# ePro.net
KiCad netlist of a schematic drawn in EAGLE
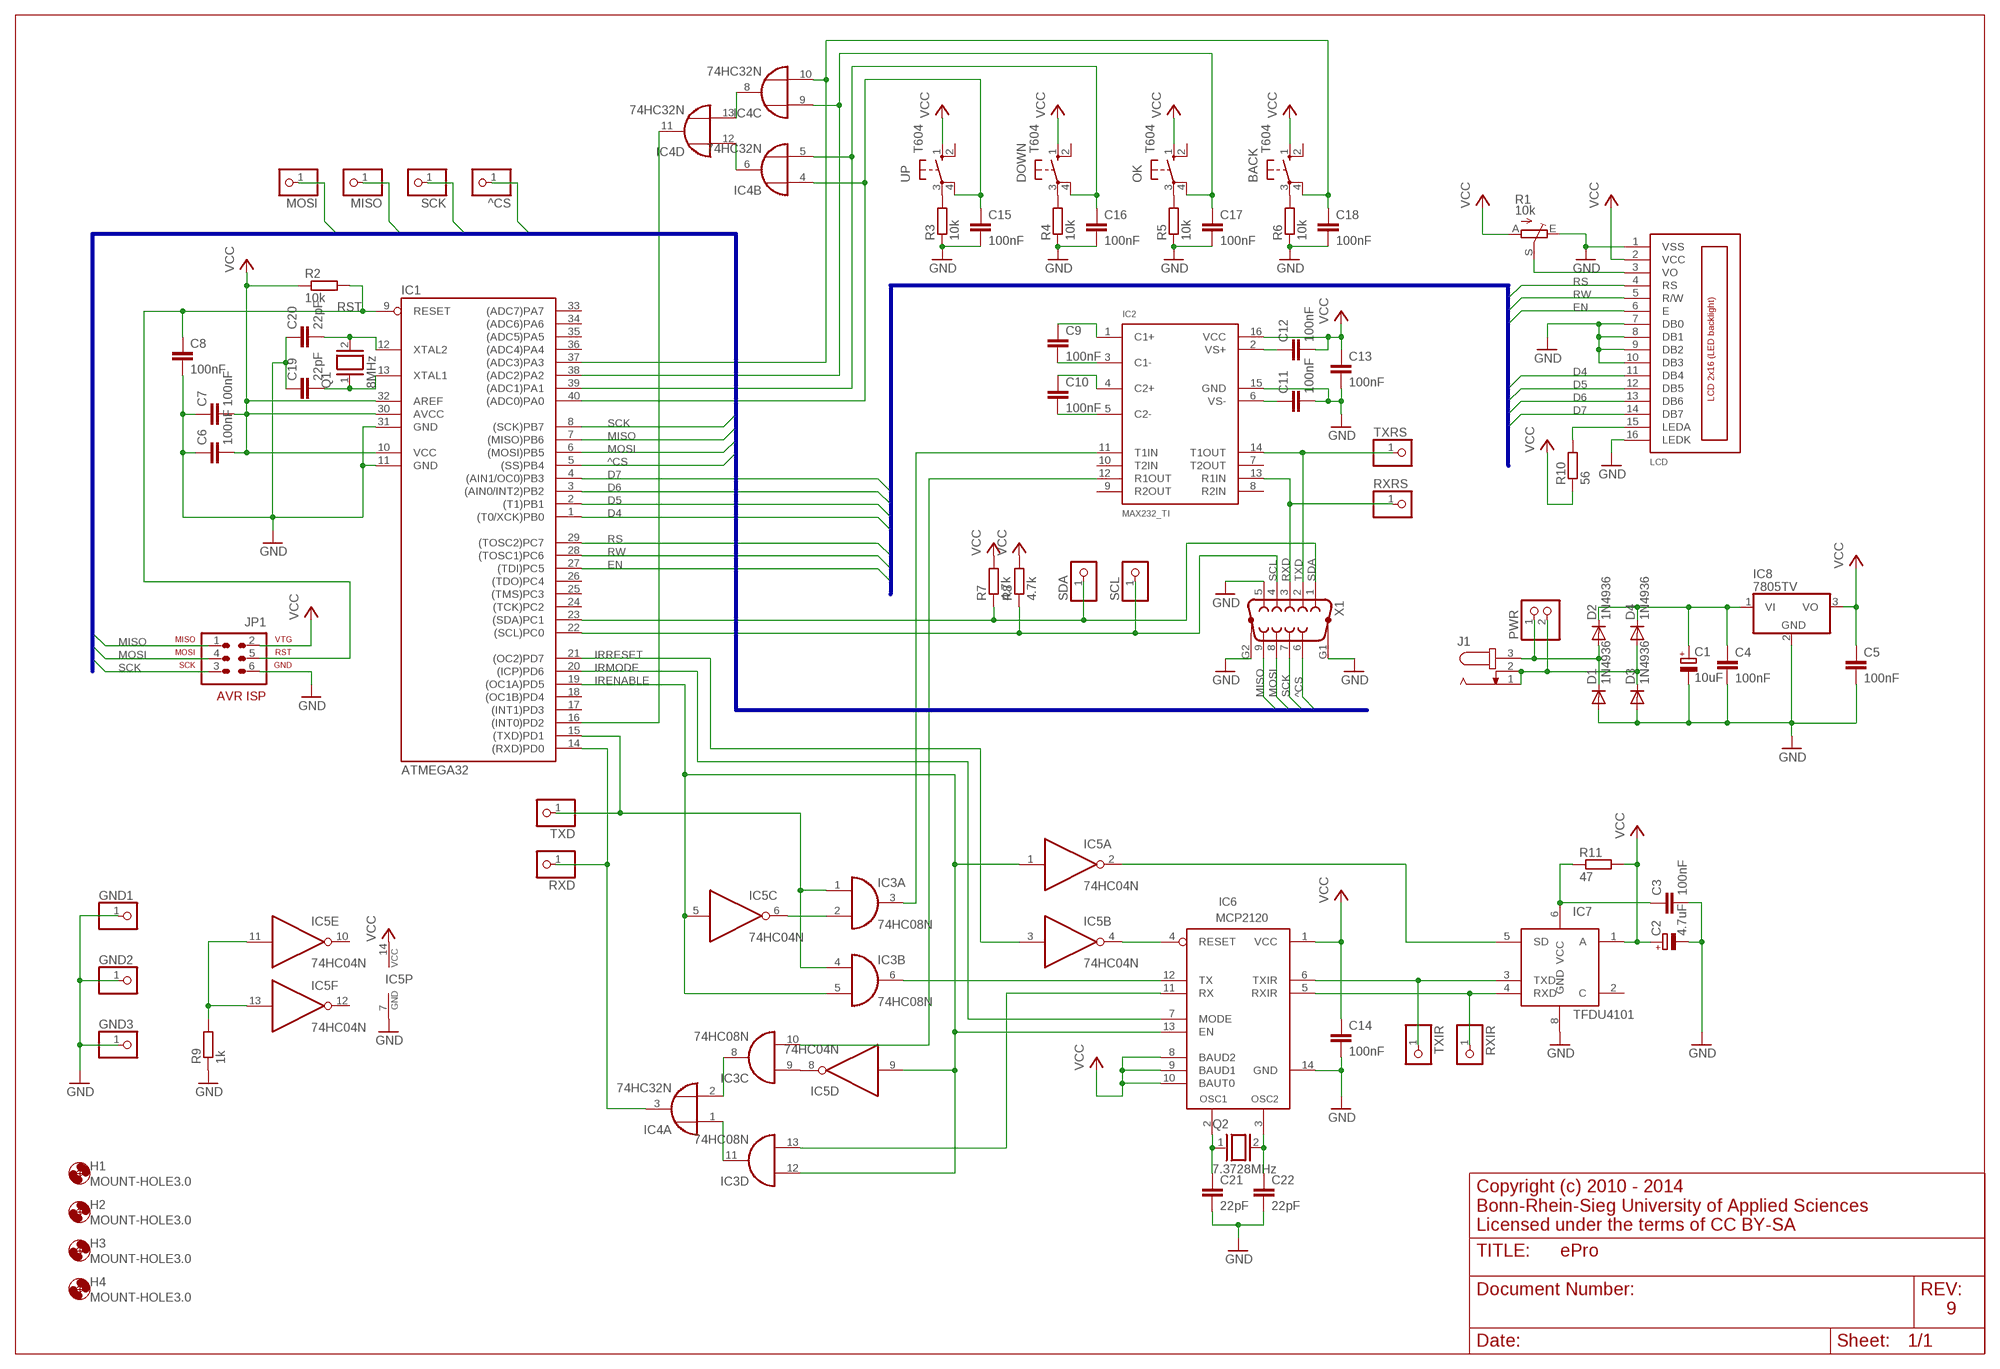
[diagram p0: schematic, sheet 1]

(export (version "E")
  (design (tool "Eeschema 10.0.6"))
  (components
    (comp (ref "BACK")
      (value "T604")
      (footprint "eagle-import:T602_604")
      (libsource (lib "eagle-import") (part "T604"))
    )
    (comp (ref "C1")
      (value "10uF")
      (footprint "eagle-import:B45181B")
      (libsource (lib "eagle-import") (part "CPOL-EUB45181B"))
    )
    (comp (ref "C2")
      (value "4.7uF")
      (footprint "eagle-import:B45181B")
      (libsource (lib "eagle-import") (part "CPOL-EUB45181B"))
    )
    (comp (ref "C3")
      (value "100nF")
      (footprint "eagle-import:C025-024X044")
      (libsource (lib "eagle-import") (part "C-EU025-024X044"))
    )
    (comp (ref "C4")
      (value "100nF")
      (footprint "eagle-import:C025-024X044")
      (libsource (lib "eagle-import") (part "C-EU025-024X044"))
    )
    (comp (ref "C5")
      (value "100nF")
      (footprint "eagle-import:C025-024X044")
      (libsource (lib "eagle-import") (part "C-EU025-024X044"))
    )
    (comp (ref "C6")
      (value "100nF")
      (footprint "eagle-import:C025-024X044")
      (libsource (lib "eagle-import") (part "C-EU025-024X044"))
    )
    (comp (ref "C7")
      (value "100nF")
      (footprint "eagle-import:C025-024X044")
      (libsource (lib "eagle-import") (part "C-EU025-024X044"))
    )
    (comp (ref "C8")
      (value "100nF")
      (footprint "eagle-import:C025-024X044")
      (libsource (lib "eagle-import") (part "C-EU025-024X044"))
    )
    (comp (ref "C9")
      (value "100nF")
      (footprint "eagle-import:C025-024X044")
      (libsource (lib "eagle-import") (part "C-EU025-024X044"))
    )
    (comp (ref "C10")
      (value "100nF")
      (footprint "eagle-import:C025-024X044")
      (libsource (lib "eagle-import") (part "C-EU025-024X044"))
    )
    (comp (ref "C11")
      (value "100nF")
      (footprint "eagle-import:C025-024X044")
      (libsource (lib "eagle-import") (part "C-EU025-024X044"))
    )
    (comp (ref "C12")
      (value "100nF")
      (footprint "eagle-import:C025-024X044")
      (libsource (lib "eagle-import") (part "C-EU025-024X044"))
    )
    (comp (ref "C13")
      (value "100nF")
      (footprint "eagle-import:C025-024X044")
      (libsource (lib "eagle-import") (part "C-EU025-024X044"))
    )
    (comp (ref "C14")
      (value "100nF")
      (footprint "eagle-import:C025-024X044")
      (libsource (lib "eagle-import") (part "C-EU025-024X044"))
    )
    (comp (ref "C15")
      (value "100nF")
      (footprint "eagle-import:C025-024X044")
      (libsource (lib "eagle-import") (part "C-EU025-024X044"))
    )
    (comp (ref "C16")
      (value "100nF")
      (footprint "eagle-import:C025-024X044")
      (libsource (lib "eagle-import") (part "C-EU025-024X044"))
    )
    (comp (ref "C17")
      (value "100nF")
      (footprint "eagle-import:C025-024X044")
      (libsource (lib "eagle-import") (part "C-EU025-024X044"))
    )
    (comp (ref "C18")
      (value "100nF")
      (footprint "eagle-import:C025-024X044")
      (libsource (lib "eagle-import") (part "C-EU025-024X044"))
    )
    (comp (ref "C19")
      (value "22pF")
      (footprint "eagle-import:C025-024X044")
      (libsource (lib "eagle-import") (part "resistor_C-EU025-024X044"))
    )
    (comp (ref "C20")
      (value "22pF")
      (footprint "eagle-import:C025-024X044")
      (libsource (lib "eagle-import") (part "resistor_C-EU025-024X044"))
    )
    (comp (ref "C21")
      (value "22pF")
      (footprint "eagle-import:C025-024X044")
      (libsource (lib "eagle-import") (part "resistor_C-EU025-024X044"))
    )
    (comp (ref "C22")
      (value "22pF")
      (footprint "eagle-import:C025-024X044")
      (libsource (lib "eagle-import") (part "resistor_C-EU025-024X044"))
    )
    (comp (ref "D1")
      (value "1N4936")
      (footprint "eagle-import:DO41-10")
      (libsource (lib "eagle-import") (part "1N4936"))
    )
    (comp (ref "D2")
      (value "1N4936")
      (footprint "eagle-import:DO41-10")
      (libsource (lib "eagle-import") (part "1N4936"))
    )
    (comp (ref "D3")
      (value "1N4936")
      (footprint "eagle-import:DO41-10")
      (libsource (lib "eagle-import") (part "1N4936"))
    )
    (comp (ref "D4")
      (value "1N4936")
      (footprint "eagle-import:DO41-10")
      (libsource (lib "eagle-import") (part "1N4936"))
    )
    (comp (ref "DOWN")
      (value "T604")
      (footprint "eagle-import:T602_604")
      (libsource (lib "eagle-import") (part "T604"))
    )
    (comp (ref "GND1")
      (value "PINHD-1X1")
      (footprint "eagle-import:1X01")
      (libsource (lib "eagle-import") (part "PINHD-1X1"))
    )
    (comp (ref "GND2")
      (value "PINHD-1X1")
      (footprint "eagle-import:1X01")
      (libsource (lib "eagle-import") (part "PINHD-1X1"))
    )
    (comp (ref "GND3")
      (value "PINHD-1X1")
      (footprint "eagle-import:1X01")
      (libsource (lib "eagle-import") (part "PINHD-1X1"))
    )
    (comp (ref "H1")
      (value "MOUNT-HOLE3.0")
      (footprint "eagle-import:3,0")
      (libsource (lib "eagle-import") (part "MOUNT-HOLE3.0"))
    )
    (comp (ref "H2")
      (value "MOUNT-HOLE3.0")
      (footprint "eagle-import:3,0")
      (libsource (lib "eagle-import") (part "MOUNT-HOLE3.0"))
    )
    (comp (ref "H3")
      (value "MOUNT-HOLE3.0")
      (footprint "eagle-import:3,0")
      (libsource (lib "eagle-import") (part "MOUNT-HOLE3.0"))
    )
    (comp (ref "H4")
      (value "MOUNT-HOLE3.0")
      (footprint "eagle-import:3,0")
      (libsource (lib "eagle-import") (part "MOUNT-HOLE3.0"))
    )
    (comp (ref "IC1")
      (value "ATMEGA32")
      (footprint "eagle-import:DIL40")
      (libsource (lib "eagle-import") (part "MEGA32-P"))
    )
    (comp (ref "IC2")
      (value "MAX232_TI")
      (footprint "eagle-import:DIL16")
      (libsource (lib "eagle-import") (part "MAX232_TI"))
    )
    (comp (ref "IC3")
      (value "74HC08N")
      (footprint "eagle-import:DIL14")
      (libsource (lib "eagle-import") (part "7408NHC"))
    )
    (comp (ref "IC4")
      (value "74HC32N")
      (footprint "eagle-import:DIL14")
      (libsource (lib "eagle-import") (part "7432NHC"))
    )
    (comp (ref "IC5")
      (value "74HC04N")
      (footprint "eagle-import:DIL14")
      (libsource (lib "eagle-import") (part "7404NHC"))
    )
    (comp (ref "IC6")
      (value "MCP2120")
      (footprint "eagle-import:DIL14")
      (libsource (lib "eagle-import") (part "MCP2120-P"))
    )
    (comp (ref "IC7")
      (value "TFDU4101")
      (footprint "eagle-import:U")
      (libsource (lib "eagle-import") (part "TFDU4101"))
    )
    (comp (ref "IC8")
      (value "7805TV")
      (footprint "eagle-import:TO220V")
      (libsource (lib "eagle-import") (part "78TV05"))
    )
    (comp (ref "J1")
      (value "JACK-PLUG1")
      (footprint "eagle-import:SPC4078")
      (libsource (lib "eagle-import") (part "JACK-PLUG1"))
    )
    (comp (ref "JP1")
      (value "AVR-ISP-6")
      (footprint "eagle-import:AVR-ISP-6")
      (libsource (lib "eagle-import") (part "AVR-ISP-6"))
    )
    (comp (ref "LCD")
      (value "LCD_2X16_SIL")
      (footprint "eagle-import:HY-1602F")
      (libsource (lib "eagle-import") (part "LCD_2X16_SIL"))
    )
    (comp (ref "MISO")
      (value "PINHD-1X1")
      (footprint "eagle-import:1X01")
      (libsource (lib "eagle-import") (part "PINHD-1X1"))
    )
    (comp (ref "MOSI")
      (value "PINHD-1X1")
      (footprint "eagle-import:1X01")
      (libsource (lib "eagle-import") (part "PINHD-1X1"))
    )
    (comp (ref "OK")
      (value "T604")
      (footprint "eagle-import:T602_604")
      (libsource (lib "eagle-import") (part "T604"))
    )
    (comp (ref "PWR")
      (value "PINHD-1X2")
      (footprint "eagle-import:1X02")
      (libsource (lib "eagle-import") (part "PINHD-1X2"))
    )
    (comp (ref "Q1")
      (value "8MHz")
      (footprint "eagle-import:QS")
      (libsource (lib "eagle-import") (part "XTAL/S"))
    )
    (comp (ref "Q2")
      (value "7.3728MHz")
      (footprint "eagle-import:QS")
      (libsource (lib "eagle-import") (part "XTAL/S"))
    )
    (comp (ref "R1")
      (value "10k")
      (footprint "eagle-import:PT-10S")
      (libsource (lib "eagle-import") (part "TRIM_EU-PT10S"))
    )
    (comp (ref "R2")
      (value "10k")
      (footprint "eagle-import:0204_7")
      (libsource (lib "eagle-import") (part "R-EU_0204/7"))
    )
    (comp (ref "R3")
      (value "10k")
      (footprint "eagle-import:0204_7")
      (libsource (lib "eagle-import") (part "resistor_R-EU_0204/7"))
    )
    (comp (ref "R4")
      (value "10k")
      (footprint "eagle-import:0204_7")
      (libsource (lib "eagle-import") (part "resistor_R-EU_0204/7"))
    )
    (comp (ref "R5")
      (value "10k")
      (footprint "eagle-import:0204_7")
      (libsource (lib "eagle-import") (part "resistor_R-EU_0204/7"))
    )
    (comp (ref "R6")
      (value "10k")
      (footprint "eagle-import:0204_7")
      (libsource (lib "eagle-import") (part "resistor_R-EU_0204/7"))
    )
    (comp (ref "R7")
      (value "4.7k")
      (footprint "eagle-import:0204_7")
      (libsource (lib "eagle-import") (part "resistor_R-EU_0204/7"))
    )
    (comp (ref "R8")
      (value "4.7k")
      (footprint "eagle-import:0204_7")
      (libsource (lib "eagle-import") (part "resistor_R-EU_0204/7"))
    )
    (comp (ref "R9")
      (value "1k")
      (footprint "eagle-import:0204_7")
      (libsource (lib "eagle-import") (part "resistor_R-EU_0204/7"))
    )
    (comp (ref "R10")
      (value "56")
      (footprint "eagle-import:0204_7")
      (libsource (lib "eagle-import") (part "R-EU_0204/7"))
    )
    (comp (ref "R11")
      (value "47")
      (footprint "eagle-import:0204_7")
      (libsource (lib "eagle-import") (part "R-EU_0204/7"))
    )
    (comp (ref "RXD")
      (value "PINHD-1X1")
      (footprint "eagle-import:1X01")
      (libsource (lib "eagle-import") (part "PINHD-1X1"))
    )
    (comp (ref "RXIR")
      (value "PINHD-1X1")
      (footprint "eagle-import:1X01")
      (libsource (lib "eagle-import") (part "PINHD-1X1"))
    )
    (comp (ref "RXRS")
      (value "PINHD-1X1")
      (footprint "eagle-import:1X01")
      (libsource (lib "eagle-import") (part "PINHD-1X1"))
    )
    (comp (ref "SCK")
      (value "PINHD-1X1")
      (footprint "eagle-import:1X01")
      (libsource (lib "eagle-import") (part "PINHD-1X1"))
    )
    (comp (ref "SCL")
      (value "PINHD-1X1")
      (footprint "eagle-import:1X01")
      (libsource (lib "eagle-import") (part "PINHD-1X1"))
    )
    (comp (ref "SDA")
      (value "PINHD-1X1")
      (footprint "eagle-import:1X01")
      (libsource (lib "eagle-import") (part "PINHD-1X1"))
    )
    (comp (ref "TXD")
      (value "PINHD-1X1")
      (footprint "eagle-import:1X01")
      (libsource (lib "eagle-import") (part "PINHD-1X1"))
    )
    (comp (ref "TXIR")
      (value "PINHD-1X1")
      (footprint "eagle-import:1X01")
      (libsource (lib "eagle-import") (part "PINHD-1X1"))
    )
    (comp (ref "TXRS")
      (value "PINHD-1X1")
      (footprint "eagle-import:1X01")
      (libsource (lib "eagle-import") (part "PINHD-1X1"))
    )
    (comp (ref "UP")
      (value "T604")
      (footprint "eagle-import:T602_604")
      (libsource (lib "eagle-import") (part "T604"))
    )
    (comp (ref "X1")
      (value "F09HP")
      (footprint "eagle-import:F09HP")
      (libsource (lib "eagle-import") (part "F09HP"))
    )
    (comp (ref "^CS")
      (value "PINHD-1X1")
      (footprint "eagle-import:1X01")
      (libsource (lib "eagle-import") (part "PINHD-1X1"))
    )
  )
  (nets
    (net (code "1") (name "/D4") (class "Default")
      (node (ref "IC1") (pin "1") (pinfunction "(T0/XCK)PB0_1") (pintype "bidirectional"))
      (node (ref "LCD") (pin "11") (pinfunction "DB4_11") (pintype "bidirectional"))
    )
    (net (code "2") (name "/D5") (class "Default")
      (node (ref "IC1") (pin "2") (pinfunction "(T1)PB1_2") (pintype "bidirectional"))
      (node (ref "LCD") (pin "12") (pinfunction "DB5_12") (pintype "bidirectional"))
    )
    (net (code "3") (name "/D6") (class "Default")
      (node (ref "IC1") (pin "3") (pinfunction "(AIN0/INT2)PB2_3") (pintype "bidirectional"))
      (node (ref "LCD") (pin "13") (pinfunction "DB6_13") (pintype "bidirectional"))
    )
    (net (code "4") (name "/D7") (class "Default")
      (node (ref "IC1") (pin "4") (pinfunction "(AIN1/OC0)PB3_4") (pintype "bidirectional"))
      (node (ref "LCD") (pin "14") (pinfunction "DB7_14") (pintype "bidirectional"))
    )
    (net (code "5") (name "/EN") (class "Default")
      (node (ref "IC1") (pin "27") (pinfunction "(TDI)PC5_27") (pintype "bidirectional"))
      (node (ref "LCD") (pin "6") (pinfunction "E_6") (pintype "input"))
    )
    (net (code "6") (name "/IRENABLE") (class "Default")
      (node (ref "IC1") (pin "19") (pinfunction "(OC1A)PD5_19") (pintype "bidirectional"))
      (node (ref "IC3") (pin "12") (pinfunction "I0_12") (pintype "input"))
      (node (ref "IC3") (pin "5") (pinfunction "I1_5") (pintype "input"))
      (node (ref "IC5") (pin "1") (pinfunction "I_1") (pintype "input"))
      (node (ref "IC5") (pin "5") (pinfunction "I_5") (pintype "input"))
      (node (ref "IC5") (pin "9") (pinfunction "I_9") (pintype "input"))
      (node (ref "IC6") (pin "13") (pinfunction "EN_13") (pintype "input"))
    )
    (net (code "7") (name "/IRMODE") (class "Default")
      (node (ref "IC1") (pin "20") (pinfunction "(ICP)PD6_20") (pintype "bidirectional"))
      (node (ref "IC6") (pin "7") (pinfunction "MODE_7") (pintype "input"))
    )
    (net (code "8") (name "/IRRESET") (class "Default")
      (node (ref "IC1") (pin "21") (pinfunction "(OC2)PD7_21") (pintype "bidirectional"))
      (node (ref "IC5") (pin "3") (pinfunction "I_3") (pintype "input"))
    )
    (net (code "9") (name "/MISO") (class "Default")
      (node (ref "IC1") (pin "7") (pinfunction "(MISO)PB6_7") (pintype "bidirectional"))
      (node (ref "JP1") (pin "1") (pinfunction "1_1") (pintype "passive"))
      (node (ref "MISO") (pin "1") (pinfunction "1_1") (pintype "passive"))
      (node (ref "X1") (pin "9") (pinfunction "9_9") (pintype "passive"))
    )
    (net (code "10") (name "/MOSI") (class "Default")
      (node (ref "IC1") (pin "6") (pinfunction "(MOSI)PB5_6") (pintype "bidirectional"))
      (node (ref "JP1") (pin "4") (pinfunction "4_4") (pintype "passive"))
      (node (ref "MOSI") (pin "1") (pinfunction "1_1") (pintype "passive"))
      (node (ref "X1") (pin "8") (pinfunction "8_8") (pintype "passive"))
    )
    (net (code "11") (name "/RS") (class "Default")
      (node (ref "IC1") (pin "29") (pinfunction "(TOSC2)PC7_29") (pintype "bidirectional"))
      (node (ref "LCD") (pin "4") (pinfunction "RS_4") (pintype "input"))
    )
    (net (code "12") (name "/RST") (class "Default")
      (node (ref "C8") (pin "1") (pinfunction "1_1") (pintype "passive"))
      (node (ref "IC1") (pin "9") (pinfunction "RESET_9") (pintype "input"))
      (node (ref "JP1") (pin "5") (pinfunction "5_5") (pintype "passive"))
      (node (ref "R2") (pin "2") (pinfunction "2_2") (pintype "passive"))
    )
    (net (code "13") (name "/RW") (class "Default")
      (node (ref "IC1") (pin "28") (pinfunction "(TOSC1)PC6_28") (pintype "bidirectional"))
      (node (ref "LCD") (pin "5") (pinfunction "R/W_5") (pintype "input"))
    )
    (net (code "14") (name "/RXD") (class "Default")
      (node (ref "IC2") (pin "13") (pinfunction "R1IN_13") (pintype "bidirectional"))
      (node (ref "RXRS") (pin "1") (pinfunction "1_1") (pintype "passive"))
      (node (ref "X1") (pin "3") (pinfunction "3_3") (pintype "passive"))
    )
    (net (code "15") (name "/SCK") (class "Default")
      (node (ref "IC1") (pin "8") (pinfunction "(SCK)PB7_8") (pintype "bidirectional"))
      (node (ref "JP1") (pin "3") (pinfunction "3_3") (pintype "passive"))
      (node (ref "SCK") (pin "1") (pinfunction "1_1") (pintype "passive"))
      (node (ref "X1") (pin "7") (pinfunction "7_7") (pintype "passive"))
    )
    (net (code "16") (name "/SCL") (class "Default")
      (node (ref "IC1") (pin "22") (pinfunction "(SCL)PC0_22") (pintype "bidirectional"))
      (node (ref "R8") (pin "1") (pinfunction "1_1") (pintype "passive"))
      (node (ref "SCL") (pin "1") (pinfunction "1_1") (pintype "passive"))
      (node (ref "X1") (pin "4") (pinfunction "4_4") (pintype "passive"))
    )
    (net (code "17") (name "/SDA") (class "Default")
      (node (ref "IC1") (pin "23") (pinfunction "(SDA)PC1_23") (pintype "bidirectional"))
      (node (ref "R7") (pin "1") (pinfunction "1_1") (pintype "passive"))
      (node (ref "SDA") (pin "1") (pinfunction "1_1") (pintype "passive"))
      (node (ref "X1") (pin "1") (pinfunction "1_1") (pintype "passive"))
    )
    (net (code "18") (name "/TXD") (class "Default")
      (node (ref "IC2") (pin "14") (pinfunction "T1OUT_14") (pintype "bidirectional"))
      (node (ref "TXRS") (pin "1") (pinfunction "1_1") (pintype "passive"))
      (node (ref "X1") (pin "2") (pinfunction "2_2") (pintype "passive"))
    )
    (net (code "19") (name "/^CS") (class "Default")
      (node (ref "IC1") (pin "5") (pinfunction "(SS)PB4_5") (pintype "bidirectional"))
      (node (ref "X1") (pin "6") (pinfunction "6_6") (pintype "passive"))
      (node (ref "^CS") (pin "1") (pinfunction "1_1") (pintype "passive"))
    )
    (net (code "20") (name "GND") (class "Default")
      (node (ref "C1") (pin "-") (pinfunction "-_-") (pintype "passive"))
      (node (ref "C11") (pin "2") (pinfunction "2_2") (pintype "passive"))
      (node (ref "C13") (pin "2") (pinfunction "2_2") (pintype "passive"))
      (node (ref "C14") (pin "2") (pinfunction "2_2") (pintype "passive"))
      (node (ref "C15") (pin "2") (pinfunction "2_2") (pintype "passive"))
      (node (ref "C16") (pin "2") (pinfunction "2_2") (pintype "passive"))
      (node (ref "C17") (pin "2") (pinfunction "2_2") (pintype "passive"))
      (node (ref "C18") (pin "2") (pinfunction "2_2") (pintype "passive"))
      (node (ref "C19") (pin "1") (pinfunction "1_1") (pintype "passive"))
      (node (ref "C2") (pin "-") (pinfunction "-_-") (pintype "passive"))
      (node (ref "C20") (pin "1") (pinfunction "1_1") (pintype "passive"))
      (node (ref "C21") (pin "2") (pinfunction "2_2") (pintype "passive"))
      (node (ref "C22") (pin "2") (pinfunction "2_2") (pintype "passive"))
      (node (ref "C3") (pin "2") (pinfunction "2_2") (pintype "passive"))
      (node (ref "C4") (pin "2") (pinfunction "2_2") (pintype "passive"))
      (node (ref "C5") (pin "2") (pinfunction "2_2") (pintype "passive"))
      (node (ref "C6") (pin "1") (pinfunction "1_1") (pintype "passive"))
      (node (ref "C7") (pin "1") (pinfunction "1_1") (pintype "passive"))
      (node (ref "C8") (pin "2") (pinfunction "2_2") (pintype "passive"))
      (node (ref "D1") (pin "A") (pinfunction "A_A") (pintype "passive"))
      (node (ref "D3") (pin "A") (pinfunction "A_A") (pintype "passive"))
      (node (ref "GND1") (pin "1") (pinfunction "1_1") (pintype "passive"))
      (node (ref "GND2") (pin "1") (pinfunction "1_1") (pintype "passive"))
      (node (ref "GND3") (pin "1") (pinfunction "1_1") (pintype "passive"))
      (node (ref "IC1") (pin "11") (pinfunction "GND_11") (pintype "power_in"))
      (node (ref "IC1") (pin "31") (pinfunction "GND_31") (pintype "power_in"))
      (node (ref "IC2") (pin "15") (pinfunction "GND_15") (pintype "bidirectional"))
      (node (ref "IC5") (pin "7") (pinfunction "GND_7") (pintype "power_in"))
      (node (ref "IC6") (pin "14") (pinfunction "GND_14") (pintype "power_in"))
      (node (ref "IC7") (pin "8") (pinfunction "GND_8") (pintype "power_in"))
      (node (ref "IC8") (pin "2") (pinfunction "GND_2") (pintype "passive"))
      (node (ref "JP1") (pin "6") (pinfunction "6_6") (pintype "passive"))
      (node (ref "LCD") (pin "1") (pinfunction "VSS_1") (pintype "power_in"))
      (node (ref "LCD") (pin "10") (pinfunction "DB3_10") (pintype "bidirectional"))
      (node (ref "LCD") (pin "16") (pinfunction "LEDK_16") (pintype "passive"))
      (node (ref "LCD") (pin "7") (pinfunction "DB0_7") (pintype "bidirectional"))
      (node (ref "LCD") (pin "8") (pinfunction "DB1_8") (pintype "bidirectional"))
      (node (ref "LCD") (pin "9") (pinfunction "DB2_9") (pintype "bidirectional"))
      (node (ref "R1") (pin "E") (pinfunction "E_E") (pintype "passive"))
      (node (ref "R3") (pin "1") (pinfunction "1_1") (pintype "passive"))
      (node (ref "R4") (pin "1") (pinfunction "1_1") (pintype "passive"))
      (node (ref "R5") (pin "1") (pinfunction "1_1") (pintype "passive"))
      (node (ref "R6") (pin "1") (pinfunction "1_1") (pintype "passive"))
      (node (ref "R9") (pin "1") (pinfunction "1_1") (pintype "passive"))
      (node (ref "X1") (pin "5") (pinfunction "5_5") (pintype "passive"))
      (node (ref "X1") (pin "G1") (pinfunction "G1_G1") (pintype "passive"))
      (node (ref "X1") (pin "G2") (pinfunction "G2_G2") (pintype "passive"))
    )
    (net (code "21") (name "Net-(BACK-Pad3)") (class "Default")
      (node (ref "BACK") (pin "3") (pinfunction "3_3") (pintype "passive"))
      (node (ref "R6") (pin "2") (pinfunction "2_2") (pintype "passive"))
    )
    (net (code "22") (name "Net-(D1-PadC)") (class "Default")
      (node (ref "D1") (pin "C") (pinfunction "C_C") (pintype "passive"))
      (node (ref "D2") (pin "A") (pinfunction "A_A") (pintype "passive"))
      (node (ref "J1") (pin "3") (pinfunction "3_3") (pintype "passive"))
      (node (ref "PWR") (pin "1") (pinfunction "1_1") (pintype "passive"))
    )
    (net (code "23") (name "Net-(D3-PadC)") (class "Default")
      (node (ref "D3") (pin "C") (pinfunction "C_C") (pintype "passive"))
      (node (ref "D4") (pin "A") (pinfunction "A_A") (pintype "passive"))
      (node (ref "J1") (pin "1") (pinfunction "1_1") (pintype "passive"))
      (node (ref "J1") (pin "2") (pinfunction "2_2") (pintype "passive"))
      (node (ref "PWR") (pin "2") (pinfunction "2_2") (pintype "passive"))
    )
    (net (code "24") (name "Net-(DOWN-Pad3)") (class "Default")
      (node (ref "DOWN") (pin "3") (pinfunction "3_3") (pintype "passive"))
      (node (ref "R4") (pin "2") (pinfunction "2_2") (pintype "passive"))
    )
    (net (code "25") (name "Net-(IC1-(ADC0)PA0)") (class "Default")
      (node (ref "C15") (pin "1") (pinfunction "1_1") (pintype "passive"))
      (node (ref "IC1") (pin "40") (pinfunction "(ADC0)PA0_40") (pintype "bidirectional"))
      (node (ref "IC4") (pin "4") (pinfunction "I0_4") (pintype "input"))
      (node (ref "UP") (pin "4") (pinfunction "4_4") (pintype "passive"))
    )
    (net (code "26") (name "Net-(IC1-(ADC1)PA1)") (class "Default")
      (node (ref "C16") (pin "1") (pinfunction "1_1") (pintype "passive"))
      (node (ref "DOWN") (pin "4") (pinfunction "4_4") (pintype "passive"))
      (node (ref "IC1") (pin "39") (pinfunction "(ADC1)PA1_39") (pintype "bidirectional"))
      (node (ref "IC4") (pin "5") (pinfunction "I1_5") (pintype "input"))
    )
    (net (code "27") (name "Net-(IC1-(ADC2)PA2)") (class "Default")
      (node (ref "C17") (pin "1") (pinfunction "1_1") (pintype "passive"))
      (node (ref "IC1") (pin "38") (pinfunction "(ADC2)PA2_38") (pintype "bidirectional"))
      (node (ref "IC4") (pin "9") (pinfunction "I0_9") (pintype "input"))
      (node (ref "OK") (pin "4") (pinfunction "4_4") (pintype "passive"))
    )
    (net (code "28") (name "Net-(IC1-(ADC3)PA3)") (class "Default")
      (node (ref "BACK") (pin "4") (pinfunction "4_4") (pintype "passive"))
      (node (ref "C18") (pin "1") (pinfunction "1_1") (pintype "passive"))
      (node (ref "IC1") (pin "37") (pinfunction "(ADC3)PA3_37") (pintype "bidirectional"))
      (node (ref "IC4") (pin "10") (pinfunction "I1_10") (pintype "input"))
    )
    (net (code "29") (name "Net-(IC1-(INT0)PD2)") (class "Default")
      (node (ref "IC1") (pin "16") (pinfunction "(INT0)PD2_16") (pintype "bidirectional"))
      (node (ref "IC4") (pin "11") (pinfunction "O_11") (pintype "output"))
    )
    (net (code "30") (name "Net-(IC1-(RXD)PD0)") (class "Default")
      (node (ref "IC1") (pin "14") (pinfunction "(RXD)PD0_14") (pintype "bidirectional"))
      (node (ref "IC4") (pin "3") (pinfunction "O_3") (pintype "output"))
      (node (ref "RXD") (pin "1") (pinfunction "1_1") (pintype "passive"))
    )
    (net (code "31") (name "Net-(IC1-(TXD)PD1)") (class "Default")
      (node (ref "IC1") (pin "15") (pinfunction "(TXD)PD1_15") (pintype "bidirectional"))
      (node (ref "IC3") (pin "1") (pinfunction "I0_1") (pintype "input"))
      (node (ref "IC3") (pin "4") (pinfunction "I0_4") (pintype "input"))
      (node (ref "TXD") (pin "1") (pinfunction "1_1") (pintype "passive"))
    )
    (net (code "32") (name "Net-(IC1-XTAL1)") (class "Default")
      (node (ref "C19") (pin "2") (pinfunction "2_2") (pintype "passive"))
      (node (ref "IC1") (pin "13") (pinfunction "XTAL1_13") (pintype "bidirectional"))
      (node (ref "Q1") (pin "1") (pinfunction "1_1") (pintype "passive"))
    )
    (net (code "33") (name "Net-(IC1-XTAL2)") (class "Default")
      (node (ref "C20") (pin "2") (pinfunction "2_2") (pintype "passive"))
      (node (ref "IC1") (pin "12") (pinfunction "XTAL2_12") (pintype "bidirectional"))
      (node (ref "Q1") (pin "2") (pinfunction "2_2") (pintype "passive"))
    )
    (net (code "34") (name "Net-(IC2-C1+)") (class "Default")
      (node (ref "C9") (pin "1") (pinfunction "1_1") (pintype "passive"))
      (node (ref "IC2") (pin "1") (pinfunction "C1+_1") (pintype "bidirectional"))
    )
    (net (code "35") (name "Net-(IC2-C1-)") (class "Default")
      (node (ref "C9") (pin "2") (pinfunction "2_2") (pintype "passive"))
      (node (ref "IC2") (pin "3") (pinfunction "C1-_3") (pintype "bidirectional"))
    )
    (net (code "36") (name "Net-(IC2-C2+)") (class "Default")
      (node (ref "C10") (pin "1") (pinfunction "1_1") (pintype "passive"))
      (node (ref "IC2") (pin "4") (pinfunction "C2+_4") (pintype "bidirectional"))
    )
    (net (code "37") (name "Net-(IC2-C2-)") (class "Default")
      (node (ref "C10") (pin "2") (pinfunction "2_2") (pintype "passive"))
      (node (ref "IC2") (pin "5") (pinfunction "C2-_5") (pintype "bidirectional"))
    )
    (net (code "38") (name "Net-(IC2-R1OUT)") (class "Default")
      (node (ref "IC2") (pin "12") (pinfunction "R1OUT_12") (pintype "bidirectional"))
      (node (ref "IC3") (pin "10") (pinfunction "I1_10") (pintype "input"))
    )
    (net (code "39") (name "Net-(IC2-T1IN)") (class "Default")
      (node (ref "IC2") (pin "11") (pinfunction "T1IN_11") (pintype "bidirectional"))
      (node (ref "IC3") (pin "3") (pinfunction "O_3") (pintype "output"))
    )
    (net (code "40") (name "Net-(IC2-VS+)") (class "Default")
      (node (ref "C12") (pin "1") (pinfunction "1_1") (pintype "passive"))
      (node (ref "IC2") (pin "2") (pinfunction "VS+_2") (pintype "bidirectional"))
    )
    (net (code "41") (name "Net-(IC2-VS-)") (class "Default")
      (node (ref "C11") (pin "1") (pinfunction "1_1") (pintype "passive"))
      (node (ref "IC2") (pin "6") (pinfunction "VS-_6") (pintype "bidirectional"))
    )
    (net (code "42") (name "Net-(IC3A-I1)") (class "Default")
      (node (ref "IC3") (pin "2") (pinfunction "I1_2") (pintype "input"))
      (node (ref "IC5") (pin "6") (pinfunction "O_6") (pintype "output"))
    )
    (net (code "43") (name "Net-(IC3B-O)") (class "Default")
      (node (ref "IC3") (pin "6") (pinfunction "O_6") (pintype "output"))
      (node (ref "IC6") (pin "12") (pinfunction "TX_12") (pintype "input"))
    )
    (net (code "44") (name "Net-(IC3C-I0)") (class "Default")
      (node (ref "IC3") (pin "9") (pinfunction "I0_9") (pintype "input"))
      (node (ref "IC5") (pin "8") (pinfunction "O_8") (pintype "output"))
    )
    (net (code "45") (name "Net-(IC3C-O)") (class "Default")
      (node (ref "IC3") (pin "8") (pinfunction "O_8") (pintype "output"))
      (node (ref "IC4") (pin "2") (pinfunction "I1_2") (pintype "input"))
    )
    (net (code "46") (name "Net-(IC3D-I1)") (class "Default")
      (node (ref "IC3") (pin "13") (pinfunction "I1_13") (pintype "input"))
      (node (ref "IC6") (pin "11") (pinfunction "RX_11") (pintype "output"))
    )
    (net (code "47") (name "Net-(IC3D-O)") (class "Default")
      (node (ref "IC3") (pin "11") (pinfunction "O_11") (pintype "output"))
      (node (ref "IC4") (pin "1") (pinfunction "I0_1") (pintype "input"))
    )
    (net (code "48") (name "Net-(IC4B-O)") (class "Default")
      (node (ref "IC4") (pin "12") (pinfunction "I0_12") (pintype "input"))
      (node (ref "IC4") (pin "6") (pinfunction "O_6") (pintype "output"))
    )
    (net (code "49") (name "Net-(IC4C-O)") (class "Default")
      (node (ref "IC4") (pin "13") (pinfunction "I1_13") (pintype "input"))
      (node (ref "IC4") (pin "8") (pinfunction "O_8") (pintype "output"))
    )
    (net (code "50") (name "Net-(IC5A-O)") (class "Default")
      (node (ref "IC5") (pin "2") (pinfunction "O_2") (pintype "output"))
      (node (ref "IC7") (pin "5") (pinfunction "SD_5") (pintype "input"))
    )
    (net (code "51") (name "Net-(IC5B-O)") (class "Default")
      (node (ref "IC5") (pin "4") (pinfunction "O_4") (pintype "output"))
      (node (ref "IC6") (pin "4") (pinfunction "RESET_4") (pintype "bidirectional"))
    )
    (net (code "52") (name "Net-(IC5E-I)") (class "Default")
      (node (ref "IC5") (pin "11") (pinfunction "I_11") (pintype "input"))
      (node (ref "IC5") (pin "13") (pinfunction "I_13") (pintype "input"))
      (node (ref "R9") (pin "2") (pinfunction "2_2") (pintype "passive"))
    )
    (net (code "53") (name "Net-(IC6-OSC1)") (class "Default")
      (node (ref "C21") (pin "1") (pinfunction "1_1") (pintype "passive"))
      (node (ref "IC6") (pin "2") (pinfunction "OSC1_2") (pintype "input"))
      (node (ref "Q2") (pin "1") (pinfunction "1_1") (pintype "passive"))
    )
    (net (code "54") (name "Net-(IC6-OSC2)") (class "Default")
      (node (ref "C22") (pin "1") (pinfunction "1_1") (pintype "passive"))
      (node (ref "IC6") (pin "3") (pinfunction "OSC2_3") (pintype "output"))
      (node (ref "Q2") (pin "2") (pinfunction "2_2") (pintype "passive"))
    )
    (net (code "55") (name "Net-(IC6-RXIR)") (class "Default")
      (node (ref "IC6") (pin "5") (pinfunction "RXIR_5") (pintype "input"))
      (node (ref "IC7") (pin "4") (pinfunction "RXD_4") (pintype "output"))
      (node (ref "RXIR") (pin "1") (pinfunction "1_1") (pintype "passive"))
    )
    (net (code "56") (name "Net-(IC6-TXIR)") (class "Default")
      (node (ref "IC6") (pin "6") (pinfunction "TXIR_6") (pintype "output"))
      (node (ref "IC7") (pin "3") (pinfunction "TXD_3") (pintype "input"))
      (node (ref "TXIR") (pin "1") (pinfunction "1_1") (pintype "passive"))
    )
    (net (code "57") (name "Net-(IC7-VCC)") (class "Default")
      (node (ref "C3") (pin "1") (pinfunction "1_1") (pintype "passive"))
      (node (ref "IC7") (pin "6") (pinfunction "VCC_6") (pintype "power_in"))
      (node (ref "R11") (pin "1") (pinfunction "1_1") (pintype "passive"))
    )
    (net (code "58") (name "Net-(IC8-VI)") (class "Default")
      (node (ref "C1") (pin "+") (pinfunction "+_+") (pintype "passive"))
      (node (ref "C4") (pin "1") (pinfunction "1_1") (pintype "passive"))
      (node (ref "D2") (pin "C") (pinfunction "C_C") (pintype "passive"))
      (node (ref "D4") (pin "C") (pinfunction "C_C") (pintype "passive"))
      (node (ref "IC8") (pin "1") (pinfunction "VI_1") (pintype "input"))
    )
    (net (code "59") (name "Net-(LCD-LEDA)") (class "Default")
      (node (ref "LCD") (pin "15") (pinfunction "LEDA_15") (pintype "passive"))
      (node (ref "R10") (pin "2") (pinfunction "2_2") (pintype "passive"))
    )
    (net (code "60") (name "Net-(LCD-VO)") (class "Default")
      (node (ref "LCD") (pin "3") (pinfunction "VO_3") (pintype "input"))
      (node (ref "R1") (pin "S") (pinfunction "S_S") (pintype "passive"))
    )
    (net (code "61") (name "Net-(OK-Pad3)") (class "Default")
      (node (ref "OK") (pin "3") (pinfunction "3_3") (pintype "passive"))
      (node (ref "R5") (pin "2") (pinfunction "2_2") (pintype "passive"))
    )
    (net (code "62") (name "Net-(R3-Pad2)") (class "Default")
      (node (ref "R3") (pin "2") (pinfunction "2_2") (pintype "passive"))
      (node (ref "UP") (pin "3") (pinfunction "3_3") (pintype "passive"))
    )
    (net (code "63") (name "VCC") (class "Default")
      (node (ref "BACK") (pin "1") (pinfunction "1_1") (pintype "passive"))
      (node (ref "C12") (pin "2") (pinfunction "2_2") (pintype "passive"))
      (node (ref "C13") (pin "1") (pinfunction "1_1") (pintype "passive"))
      (node (ref "C14") (pin "1") (pinfunction "1_1") (pintype "passive"))
      (node (ref "C2") (pin "+") (pinfunction "+_+") (pintype "passive"))
      (node (ref "C5") (pin "1") (pinfunction "1_1") (pintype "passive"))
      (node (ref "C6") (pin "2") (pinfunction "2_2") (pintype "passive"))
      (node (ref "C7") (pin "2") (pinfunction "2_2") (pintype "passive"))
      (node (ref "DOWN") (pin "1") (pinfunction "1_1") (pintype "passive"))
      (node (ref "IC1") (pin "10") (pinfunction "VCC_10") (pintype "power_in"))
      (node (ref "IC1") (pin "30") (pinfunction "AVCC_30") (pintype "power_in"))
      (node (ref "IC1") (pin "32") (pinfunction "AREF_32") (pintype "passive"))
      (node (ref "IC2") (pin "16") (pinfunction "VCC_16") (pintype "bidirectional"))
      (node (ref "IC5") (pin "14") (pinfunction "VCC_14") (pintype "power_in"))
      (node (ref "IC6") (pin "1") (pinfunction "VCC_1") (pintype "power_in"))
      (node (ref "IC6") (pin "10") (pinfunction "BAUT0_10") (pintype "input"))
      (node (ref "IC6") (pin "8") (pinfunction "BAUD2_8") (pintype "input"))
      (node (ref "IC6") (pin "9") (pinfunction "BAUD1_9") (pintype "input"))
      (node (ref "IC7") (pin "1") (pinfunction "A_1") (pintype "bidirectional"))
      (node (ref "IC8") (pin "3") (pinfunction "VO_3") (pintype "passive"))
      (node (ref "JP1") (pin "2") (pinfunction "2_2") (pintype "passive"))
      (node (ref "LCD") (pin "2") (pinfunction "VCC_2") (pintype "power_in"))
      (node (ref "OK") (pin "1") (pinfunction "1_1") (pintype "passive"))
      (node (ref "R1") (pin "A") (pinfunction "A_A") (pintype "passive"))
      (node (ref "R10") (pin "1") (pinfunction "1_1") (pintype "passive"))
      (node (ref "R11") (pin "2") (pinfunction "2_2") (pintype "passive"))
      (node (ref "R2") (pin "1") (pinfunction "1_1") (pintype "passive"))
      (node (ref "R7") (pin "2") (pinfunction "2_2") (pintype "passive"))
      (node (ref "R8") (pin "2") (pinfunction "2_2") (pintype "passive"))
      (node (ref "UP") (pin "1") (pinfunction "1_1") (pintype "passive"))
    )
    (net (code "64") (name "unconnected-(BACK-Pad2)") (class "Default")
      (node (ref "BACK") (pin "2") (pinfunction "2_2") (pintype "passive"))
    )
    (net (code "65") (name "unconnected-(DOWN-Pad2)") (class "Default")
      (node (ref "DOWN") (pin "2") (pinfunction "2_2") (pintype "passive"))
    )
    (net (code "66") (name "unconnected-(IC1-(ADC4)PA4-Pad36)") (class "Default")
      (node (ref "IC1") (pin "36") (pinfunction "(ADC4)PA4_36") (pintype "bidirectional"))
    )
    (net (code "67") (name "unconnected-(IC1-(ADC5)PA5-Pad35)") (class "Default")
      (node (ref "IC1") (pin "35") (pinfunction "(ADC5)PA5_35") (pintype "bidirectional"))
    )
    (net (code "68") (name "unconnected-(IC1-(ADC6)PA6-Pad34)") (class "Default")
      (node (ref "IC1") (pin "34") (pinfunction "(ADC6)PA6_34") (pintype "bidirectional"))
    )
    (net (code "69") (name "unconnected-(IC1-(ADC7)PA7-Pad33)") (class "Default")
      (node (ref "IC1") (pin "33") (pinfunction "(ADC7)PA7_33") (pintype "bidirectional"))
    )
    (net (code "70") (name "unconnected-(IC1-(INT1)PD3-Pad17)") (class "Default")
      (node (ref "IC1") (pin "17") (pinfunction "(INT1)PD3_17") (pintype "bidirectional"))
    )
    (net (code "71") (name "unconnected-(IC1-(OC1B)PD4-Pad18)") (class "Default")
      (node (ref "IC1") (pin "18") (pinfunction "(OC1B)PD4_18") (pintype "bidirectional"))
    )
    (net (code "72") (name "unconnected-(IC1-(TCK)PC2-Pad24)") (class "Default")
      (node (ref "IC1") (pin "24") (pinfunction "(TCK)PC2_24") (pintype "bidirectional"))
    )
    (net (code "73") (name "unconnected-(IC1-(TDO)PC4-Pad26)") (class "Default")
      (node (ref "IC1") (pin "26") (pinfunction "(TDO)PC4_26") (pintype "bidirectional"))
    )
    (net (code "74") (name "unconnected-(IC1-(TMS)PC3-Pad25)") (class "Default")
      (node (ref "IC1") (pin "25") (pinfunction "(TMS)PC3_25") (pintype "bidirectional"))
    )
    (net (code "75") (name "unconnected-(IC2-R2IN-Pad8)") (class "Default")
      (node (ref "IC2") (pin "8") (pinfunction "R2IN_8") (pintype "bidirectional"))
    )
    (net (code "76") (name "unconnected-(IC2-R2OUT-Pad9)") (class "Default")
      (node (ref "IC2") (pin "9") (pinfunction "R2OUT_9") (pintype "bidirectional"))
    )
    (net (code "77") (name "unconnected-(IC2-T2IN-Pad10)") (class "Default")
      (node (ref "IC2") (pin "10") (pinfunction "T2IN_10") (pintype "bidirectional"))
    )
    (net (code "78") (name "unconnected-(IC2-T2OUT-Pad7)") (class "Default")
      (node (ref "IC2") (pin "7") (pinfunction "T2OUT_7") (pintype "bidirectional"))
    )
    (net (code "79") (name "unconnected-(IC5E-O-Pad10)") (class "Default")
      (node (ref "IC5") (pin "10") (pinfunction "O_10") (pintype "output"))
    )
    (net (code "80") (name "unconnected-(IC5F-O-Pad12)") (class "Default")
      (node (ref "IC5") (pin "12") (pinfunction "O_12") (pintype "output"))
    )
    (net (code "81") (name "unconnected-(IC7-C-Pad2)") (class "Default")
      (node (ref "IC7") (pin "2") (pinfunction "C_2") (pintype "bidirectional"))
    )
    (net (code "82") (name "unconnected-(OK-Pad2)") (class "Default")
      (node (ref "OK") (pin "2") (pinfunction "2_2") (pintype "passive"))
    )
    (net (code "83") (name "unconnected-(UP-Pad2)") (class "Default")
      (node (ref "UP") (pin "2") (pinfunction "2_2") (pintype "passive"))
    )
  )
)
